# tiny.net
KiCad netlist of a schematic drawn in EAGLE
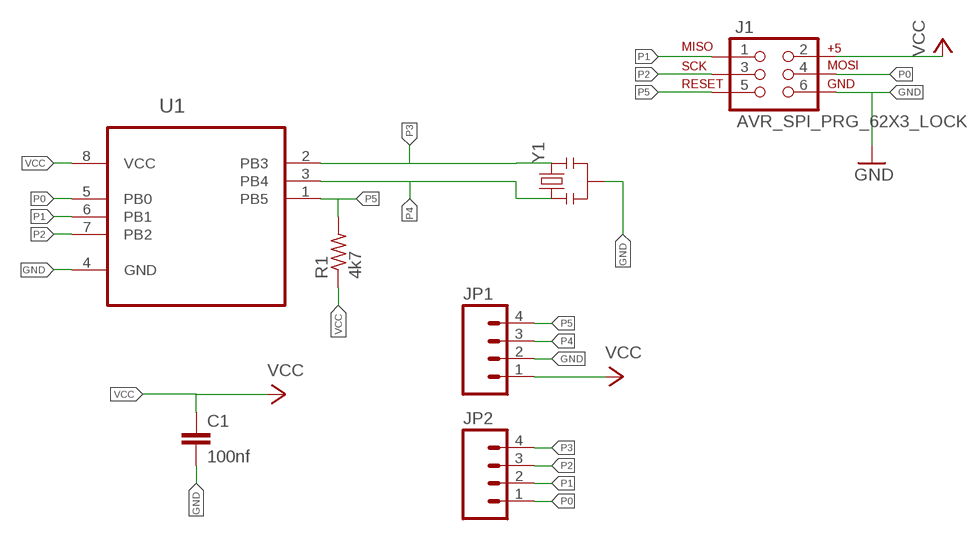
[diagram p0: schematic, sheet 1]

(export (version "E")
  (design (tool "Eeschema 10.0.6"))
  (components
    (comp (ref "C1")
      (value "100nf")
      (footprint "eagle-import:C025-024X044")
      (libsource (lib "eagle-import") (part "C-EU025-024X044"))
    )
    (comp (ref "J1")
      (value "AVR_SPI_PRG_62X3_LOCK")
      (footprint "eagle-import:2X3_LOCK")
      (libsource (lib "eagle-import") (part "AVR_SPI_PRG_62X3_LOCK"))
    )
    (comp (ref "JP1")
      (value "M04LOCK")
      (footprint "eagle-import:1X04_LOCK")
      (libsource (lib "eagle-import") (part "M04LOCK"))
    )
    (comp (ref "JP2")
      (value "M04LOCK")
      (footprint "eagle-import:1X04_LOCK")
      (libsource (lib "eagle-import") (part "M04LOCK"))
    )
    (comp (ref "R1")
      (value "4k7")
      (footprint "eagle-import:0207_12")
      (libsource (lib "eagle-import") (part "R-US_0207/12"))
    )
    (comp (ref "U1")
      (value "ATTINY25V-10PU")
      (footprint "eagle-import:DIP254P762X533-8")
      (libsource (lib "eagle-import") (part "ATTINY25V-10PU"))
    )
    (comp (ref "Y1")
      (value "RESONATORPTH")
      (footprint "eagle-import:RESONATOR-PTH")
      (libsource (lib "eagle-import") (part "RESONATORPTH"))
    )
  )
  (nets
    (net (code "1") (name "GND") (class "Default")
      (node (ref "C1") (pin "2") (pinfunction "2_2") (pintype "passive"))
      (node (ref "J1") (pin "6") (pinfunction "6_6") (pintype "passive"))
      (node (ref "JP1") (pin "2") (pinfunction "2_2") (pintype "passive"))
      (node (ref "U1") (pin "4") (pinfunction "GND_4") (pintype "passive"))
      (node (ref "Y1") (pin "2") (pinfunction "2_2") (pintype "passive"))
    )
    (net (code "2") (name "P0") (class "Default")
      (node (ref "J1") (pin "4") (pinfunction "4_4") (pintype "passive"))
      (node (ref "JP2") (pin "1") (pinfunction "1_1") (pintype "passive"))
      (node (ref "U1") (pin "5") (pinfunction "PB0_5") (pintype "bidirectional"))
    )
    (net (code "3") (name "P1") (class "Default")
      (node (ref "J1") (pin "1") (pinfunction "1_1") (pintype "passive"))
      (node (ref "JP2") (pin "2") (pinfunction "2_2") (pintype "passive"))
      (node (ref "U1") (pin "6") (pinfunction "PB1_6") (pintype "bidirectional"))
    )
    (net (code "4") (name "P2") (class "Default")
      (node (ref "J1") (pin "3") (pinfunction "3_3") (pintype "passive"))
      (node (ref "JP2") (pin "3") (pinfunction "3_3") (pintype "passive"))
      (node (ref "U1") (pin "7") (pinfunction "PB2_7") (pintype "bidirectional"))
    )
    (net (code "5") (name "P3") (class "Default")
      (node (ref "JP2") (pin "4") (pinfunction "4_4") (pintype "passive"))
      (node (ref "U1") (pin "2") (pinfunction "PB3_2") (pintype "bidirectional"))
      (node (ref "Y1") (pin "3") (pinfunction "3_3") (pintype "passive"))
    )
    (net (code "6") (name "P4") (class "Default")
      (node (ref "JP1") (pin "3") (pinfunction "3_3") (pintype "passive"))
      (node (ref "U1") (pin "3") (pinfunction "PB4_3") (pintype "bidirectional"))
      (node (ref "Y1") (pin "1") (pinfunction "1_1") (pintype "passive"))
    )
    (net (code "7") (name "P5") (class "Default")
      (node (ref "J1") (pin "5") (pinfunction "5_5") (pintype "passive"))
      (node (ref "JP1") (pin "4") (pinfunction "4_4") (pintype "passive"))
      (node (ref "R1") (pin "2") (pinfunction "2_2") (pintype "passive"))
      (node (ref "U1") (pin "1") (pinfunction "PB5_1") (pintype "bidirectional"))
    )
    (net (code "8") (name "VCC") (class "Default")
      (node (ref "C1") (pin "1") (pinfunction "1_1") (pintype "passive"))
      (node (ref "J1") (pin "2") (pinfunction "2_2") (pintype "passive"))
      (node (ref "JP1") (pin "1") (pinfunction "1_1") (pintype "passive"))
      (node (ref "R1") (pin "1") (pinfunction "1_1") (pintype "passive"))
      (node (ref "U1") (pin "8") (pinfunction "VCC_8") (pintype "power_in"))
    )
  )
)
